# Power.net
KiCad netlist of a schematic drawn in Altium Designer
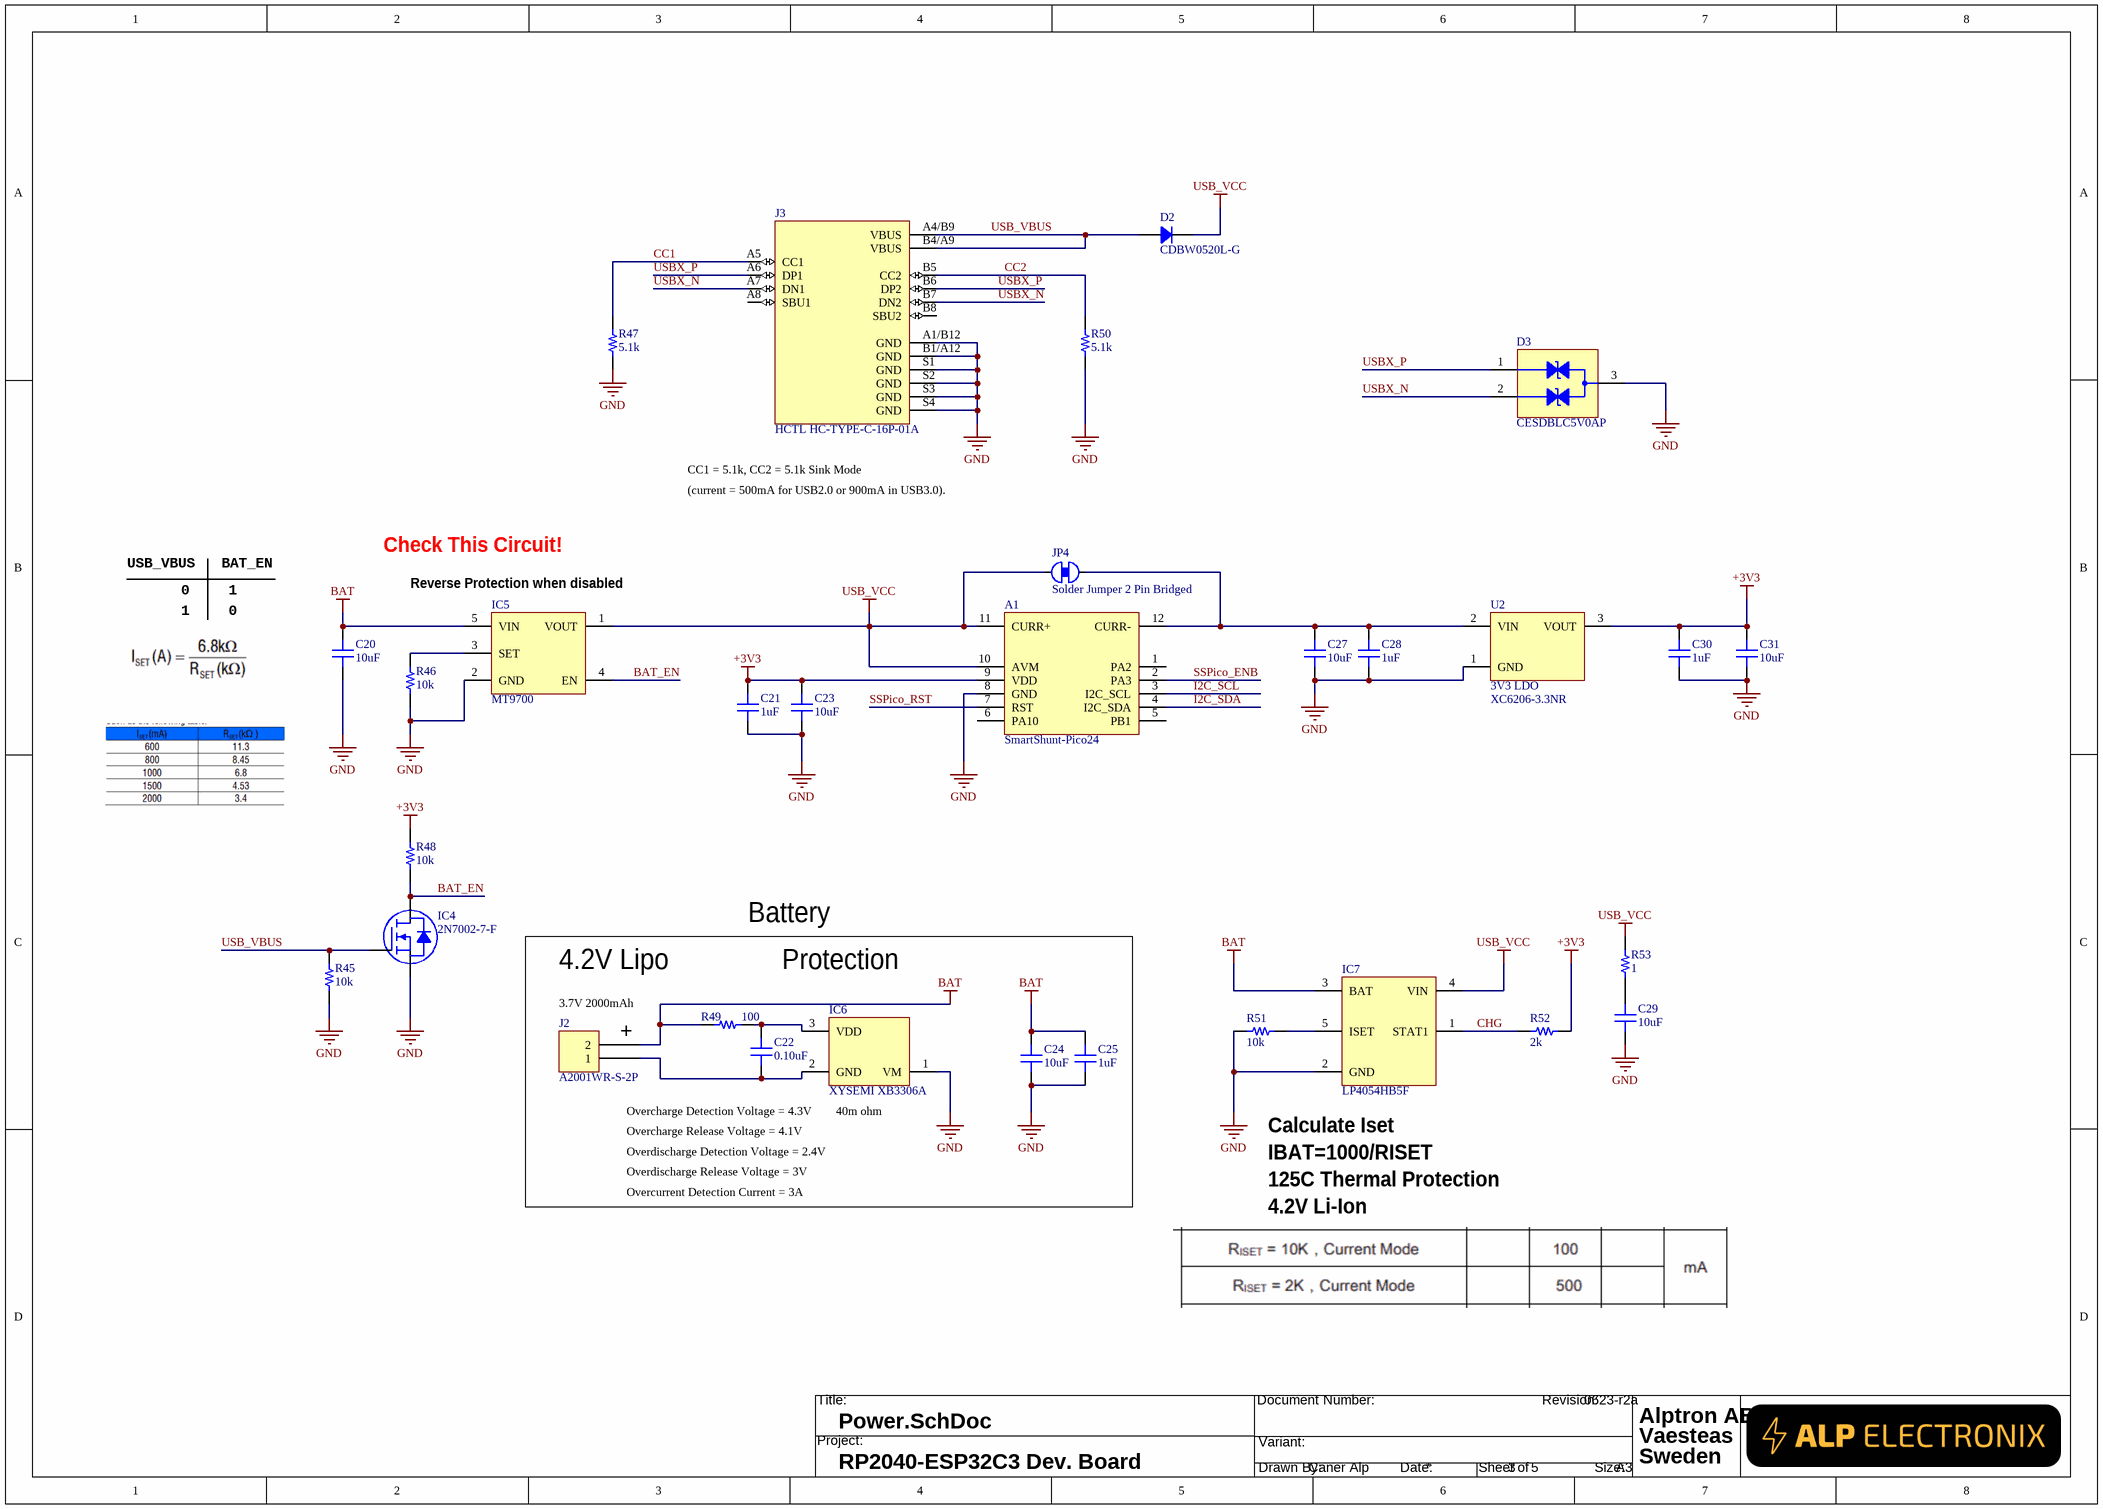
[diagram p0: Power.SchDoc]

(export (version "E")
  (design (tool "Eeschema 10.0.6"))
  (components
    (comp (ref "A1")
      (value "SmartShunt-Pico24")
      (footprint "RP2040_ESP32-C3 Dev Board PCB Lib:SmartShunt-Pico24")
      (description "Current Measurement Module")
      (libsource (lib "RP2040_ESP32-C3 Dev Board SCH Lib") (part "SmartShunt-Pico24"))
    )
    (comp (ref "C20")
      (value "10uF")
      (footprint "CAP 0603/1608")
      (description "CAP CER 10UF 6.3V X5R 0603")
      (fields
        (field (name "PART NUMBER") "GRM188R60J106ME47D")
        (field (name "MANUFACTURER") "Murata Electronics North America")
      )
      (libsource (lib "Celestial Library Database") (part "Capacitor"))
    )
    (comp (ref "C21")
      (value "1uF")
      (footprint "CAP 0402/1005")
      (description "CAP CER 1UF 6.3V X7R 0402")
      (fields
        (field (name "PART NUMBER") "GRM155R70J105KA12D")
        (field (name "MANUFACTURER") "Murata Electronics North America")
      )
      (libsource (lib "Celestial Library Database") (part "Capacitor"))
    )
    (comp (ref "C22")
      (value "0.10uF")
      (footprint "CAP 0402/1005")
      (description "CAP CER 0.1UF 10V X5R 0402")
      (fields (field (name "PART NUMBER") "LMK105BJ104KV-F") (field (name "MANUFACTURER") "Taiyo Yuden"))
      (libsource (lib "Celestial Library Database") (part "Capacitor"))
    )
    (comp (ref "C23")
      (value "10uF")
      (footprint "CAP 0603/1608")
      (description "CAP CER 10UF 6.3V X5R 0603")
      (fields
        (field (name "PART NUMBER") "GRM188R60J106ME47D")
        (field (name "MANUFACTURER") "Murata Electronics North America")
      )
      (libsource (lib "Celestial Library Database") (part "Capacitor"))
    )
    (comp (ref "C24")
      (value "10uF")
      (footprint "CAP 0603/1608")
      (description "CAP CER 10UF 6.3V X5R 0603")
      (fields
        (field (name "PART NUMBER") "GRM188R60J106ME47D")
        (field (name "MANUFACTURER") "Murata Electronics North America")
      )
      (libsource (lib "Celestial Library Database") (part "Capacitor"))
    )
    (comp (ref "C25")
      (value "1uF")
      (footprint "CAP 0402/1005")
      (description "CAP CER 1UF 6.3V X7R 0402")
      (fields
        (field (name "PART NUMBER") "GRM155R70J105KA12D")
        (field (name "MANUFACTURER") "Murata Electronics North America")
      )
      (libsource (lib "Celestial Library Database") (part "Capacitor"))
    )
    (comp (ref "C27")
      (value "10uF")
      (footprint "CAP 0603/1608")
      (description "CAP CER 10UF 6.3V X5R 0603")
      (fields
        (field (name "PART NUMBER") "GRM188R60J106ME47D")
        (field (name "MANUFACTURER") "Murata Electronics North America")
      )
      (libsource (lib "Celestial Library Database") (part "Capacitor"))
    )
    (comp (ref "C28")
      (value "1uF")
      (footprint "CAP 0402/1005")
      (description "CAP CER 1UF 6.3V X7R 0402")
      (fields
        (field (name "PART NUMBER") "GRM155R70J105KA12D")
        (field (name "MANUFACTURER") "Murata Electronics North America")
      )
      (libsource (lib "Celestial Library Database") (part "Capacitor"))
    )
    (comp (ref "C29")
      (value "10uF")
      (footprint "CAP 0603/1608")
      (description "CAP CER 10UF 6.3V X5R 0603")
      (fields
        (field (name "PART NUMBER") "GRM188R60J106ME47D")
        (field (name "MANUFACTURER") "Murata Electronics North America")
      )
      (libsource (lib "Celestial Library Database") (part "Capacitor"))
    )
    (comp (ref "C30")
      (value "1uF")
      (footprint "CAP 0402/1005")
      (description "CAP CER 1UF 6.3V X7R 0402")
      (fields
        (field (name "PART NUMBER") "GRM155R70J105KA12D")
        (field (name "MANUFACTURER") "Murata Electronics North America")
      )
      (libsource (lib "Celestial Library Database") (part "Capacitor"))
    )
    (comp (ref "C31")
      (value "10uF")
      (footprint "CAP 0603/1608")
      (description "CAP CER 10UF 6.3V X5R 0603")
      (fields
        (field (name "PART NUMBER") "GRM188R60J106ME47D")
        (field (name "MANUFACTURER") "Murata Electronics North America")
      )
      (libsource (lib "Celestial Library Database") (part "Capacitor"))
    )
    (comp (ref "D2")
      (value "CDBW0520L-G")
      (footprint "SOD-123")
      (description "DIODE SCHOTTKY 20V 500MA SOD123")
      (fields (field (name "MANUFACTURER") "Comchip Technology"))
      (libsource (lib "Celestial Altium Library - altium_library") (part "Diode"))
    )
    (comp (ref "D3")
      (value "CESDBLC5V0AP")
      (footprint "ON SEMI SOT-23-3")
      (description "TVS DIODE 24V 44V SOT23-3")
      (fields (field (name "MANUFACTURER") "ON Semiconductor"))
      (libsource (lib "Celestial Altium Library - altium_library") (part "ON SEMI SOT-23-3"))
    )
    (comp (ref "IC4")
      (value "2N7002-7-F")
      (footprint "DIODES SOT-23-3")
      (description "MOSFET N-CH 60V 115MA SOT23-3")
      (fields (field (name "MANUFACTURER") "Diodes Incorporated"))
      (libsource (lib "Celestial Library Database") (part "DIODES INC MOSFET N-CH SOT-23-3"))
    )
    (comp (ref "IC5")
      (value "MT9700")
      (footprint "RP2040_ESP32-C3 Dev Board PCB Lib:DIODES SOT-23-5 W5")
      (description "SOT-23-5 Power Distribution Switches ROHS")
      (libsource (lib "RP2040_ESP32-C3 Dev Board SCH Lib") (part "MT9700"))
    )
    (comp (ref "IC6")
      (value "XYSEMI XB3306A")
      (footprint "DIODES SOT-23-3")
      (description "IC LITHIUM BATT PROTECT SOT23-3")
      (fields (field (name "MANUFACTURER") "XYSEMI"))
      (libsource (lib "Celestial Library Database") (part "XYSEMI XB3306A"))
    )
    (comp (ref "IC7")
      (value "LP4054HB5F")
      (footprint "RP2040_ESP32-C3 Dev Board PCB Lib:DIODES SOT-23-5 W5")
      (description "600mA Standalone Linear Li-Ion Battery Charger")
      (libsource (lib "RP2040_ESP32-C3 Dev Board SCH Lib") (part "LP4054HB5F"))
    )
    (comp (ref "J2")
      (value "A2001WR-S-2P")
      (footprint "JST S2B-PH-SM4-TB")
      (description "CONN HEADER SMD R/A 2POS 2MM")
      (fields
        (field (name "PART NUMBER") "S2B-PH-SM4-TB(LF)(SN)")
        (field (name "MANUFACTURER") "JST Sales America Inc.")
      )
      (libsource (lib "Celestial Altium Library - altium_library") (part "2 Pin"))
    )
    (comp (ref "J3")
      (value "HCTL HC-TYPE-C-16P-01A")
      (footprint "RP2040_ESP32-C3 Dev Board PCB Lib:HCTL HC-TYPE-C-16P-01A")
      (description "CONN USB 2.0 TYPE-C R/A SMT")
      (fields (field (name "MANUFACTURER") "Hiro"))
      (libsource (lib "Celestial Library Database") (part "USB4110-GF-A"))
    )
    (comp (ref "JP4")
      (value "Solder Jumper 2 Pin Bridged")
      (footprint "Jumper:SolderJumper-2_P1.3mm_Bridged_RoundedPad1.0x1.5mm")
      (libsource (lib "Jumper") (part "SolderJumper_2_Bridged"))
    )
    (comp (ref "R45")
      (value "10k")
      (footprint "RES 0402/1005")
      (description "RES SMD 10K OHM 5% 1/16W 0402")
      (fields (field (name "PART NUMBER") "RC0402JR-0710KL") (field (name "MANUFACTURER") "Yageo"))
      (libsource (lib "Celestial Library Database") (part "Resistor"))
    )
    (comp (ref "R46")
      (value "10k")
      (footprint "RES 0603/1608")
      (description "RES SMD 10K OHM 5% 1/10W 0603")
      (fields
        (field (name "PART NUMBER") "ERJ-3GEYJ103V")
        (field (name "MANUFACTURER") "Panasonic Electronic Components")
      )
      (libsource (lib "Celestial Library Database") (part "Resistor"))
    )
    (comp (ref "R47")
      (value "5.1k")
      (footprint "RES 0402/1005")
      (description "RES SMD 5.1K OHM 5% 1/16W 0402")
      (fields (field (name "PART NUMBER") "RC0402JR-075K1L") (field (name "MANUFACTURER") "Yageo"))
      (libsource (lib "Celestial Library Database") (part "Resistor"))
    )
    (comp (ref "R48")
      (value "10k")
      (footprint "RES 0402/1005")
      (description "RES SMD 10K OHM 5% 1/16W 0402")
      (fields (field (name "PART NUMBER") "RC0402JR-0710KL") (field (name "MANUFACTURER") "Yageo"))
      (libsource (lib "Celestial Library Database") (part "Resistor"))
    )
    (comp (ref "R49")
      (value "100")
      (footprint "RES 0402/1005")
      (description "RES SMD 100 OHM 5% 1/16W 0402")
      (fields (field (name "PART NUMBER") "RC0402JR-07100RL") (field (name "MANUFACTURER") "Yageo"))
      (libsource (lib "Celestial Library Database") (part "Resistor"))
    )
    (comp (ref "R50")
      (value "5.1k")
      (footprint "RES 0402/1005")
      (description "RES SMD 5.1K OHM 5% 1/16W 0402")
      (fields (field (name "PART NUMBER") "RC0402JR-075K1L") (field (name "MANUFACTURER") "Yageo"))
      (libsource (lib "Celestial Library Database") (part "Resistor"))
    )
    (comp (ref "R51")
      (value "10k")
      (footprint "RES 0603/1608")
      (description "RES SMD 10K OHM 5% 1/10W 0603")
      (fields
        (field (name "PART NUMBER") "ERJ-3GEYJ103V")
        (field (name "MANUFACTURER") "Panasonic Electronic Components")
      )
      (libsource (lib "Celestial Library Database") (part "Resistor"))
    )
    (comp (ref "R52")
      (value "2k")
      (footprint "RES 0402/1005")
      (description "RES SMD 2K OHM 5% 1/16W 0402")
      (fields (field (name "PART NUMBER") "RC0402JR-072KL") (field (name "MANUFACTURER") "Yageo"))
      (libsource (lib "Celestial Library Database") (part "Resistor"))
    )
    (comp (ref "R53")
      (value "1")
      (footprint "RES 0402/1005")
      (description "RES SMD 1 OHM 5% 1/16W 0402")
      (fields (field (name "PART NUMBER") "RC0402JR-071RL") (field (name "MANUFACTURER") "Yageo"))
      (libsource (lib "Celestial Library Database") (part "Resistor"))
    )
    (comp (ref "U2")
      (value "3V3 LDO")
      (footprint "RP2040_ESP32-C3 Dev Board PCB Lib:DIODES SOT-23-3")
      (fields (field (name "MPN") "XC6206-3.3NR"))
      (libsource (lib "RP2040_ESP32-C3 Dev Board SCH Lib") (part "XC6206-3.3NR"))
    )
  )
  (nets
    (net (code "1") (name "+3V3") (class "Default")
      (node (ref "A1") (pin "9") (pinfunction "VDD_9") (pintype "passive"))
      (node (ref "C21") (pin "2") (pinfunction "2_2") (pintype "passive"))
      (node (ref "C23") (pin "2") (pinfunction "2_2") (pintype "passive"))
      (node (ref "C30") (pin "2") (pinfunction "2_2") (pintype "passive"))
      (node (ref "C31") (pin "2") (pinfunction "2_2") (pintype "passive"))
      (node (ref "R48") (pin "2") (pinfunction "2_2") (pintype "passive"))
      (node (ref "R52") (pin "2") (pinfunction "2_2") (pintype "passive"))
      (node (ref "U2") (pin "3") (pinfunction "VOUT_3") (pintype "passive"))
    )
    (net (code "2") (name "/BAT_EN") (class "Default")
      (node (ref "IC4") (pin "2") (pinfunction "D_2") (pintype "passive"))
      (node (ref "IC5") (pin "4") (pinfunction "EN_4") (pintype "passive"))
      (node (ref "R48") (pin "1") (pinfunction "1_1") (pintype "passive"))
    )
    (net (code "3") (name "/CC1") (class "Default")
      (node (ref "J3") (pin "A5") (pinfunction "CC1_A5") (pintype "bidirectional"))
      (node (ref "R47") (pin "2") (pinfunction "2_2") (pintype "passive"))
    )
    (net (code "4") (name "/CC2") (class "Default")
      (node (ref "J3") (pin "B5") (pinfunction "CC2_B5") (pintype "bidirectional"))
      (node (ref "R50") (pin "2") (pinfunction "2_2") (pintype "passive"))
    )
    (net (code "5") (name "/CHG") (class "Default")
      (node (ref "IC7") (pin "1") (pinfunction "STAT1_1") (pintype "passive"))
      (node (ref "R52") (pin "1") (pinfunction "1_1") (pintype "passive"))
    )
    (net (code "6") (name "/I2C_SCL") (class "Default")
      (node (ref "A1") (pin "3") (pinfunction "I2C_SCL_3") (pintype "passive"))
    )
    (net (code "7") (name "/I2C_SDA") (class "Default")
      (node (ref "A1") (pin "4") (pinfunction "I2C_SDA_4") (pintype "passive"))
    )
    (net (code "8") (name "/SSPico_ENB") (class "Default")
      (node (ref "A1") (pin "2") (pinfunction "PA3_2") (pintype "passive"))
    )
    (net (code "9") (name "/SSPico_RST") (class "Default")
      (node (ref "A1") (pin "7") (pinfunction "RST_7") (pintype "passive"))
    )
    (net (code "10") (name "/USBX_N") (class "Default")
      (node (ref "D3") (pin "2") (pinfunction "GND_2") (pintype "passive"))
      (node (ref "J3") (pin "A7") (pinfunction "DN1_A7") (pintype "bidirectional"))
      (node (ref "J3") (pin "B7") (pinfunction "DN2_B7") (pintype "bidirectional"))
    )
    (net (code "11") (name "/USBX_P") (class "Default")
      (node (ref "D3") (pin "1") (pinfunction "I/O_1_1") (pintype "passive"))
      (node (ref "J3") (pin "A6") (pinfunction "DP1_A6") (pintype "bidirectional"))
      (node (ref "J3") (pin "B6") (pinfunction "DP2_B6") (pintype "bidirectional"))
    )
    (net (code "12") (name "/USB_VBUS") (class "Default")
      (node (ref "D2") (pin "1") (pinfunction "1_1") (pintype "passive"))
      (node (ref "IC4") (pin "1") (pinfunction "G_1") (pintype "passive"))
      (node (ref "J3") (pin "A4/B9") (pinfunction "VBUS_A4/B9") (pintype "power_in"))
      (node (ref "J3") (pin "B4/A9") (pinfunction "VBUS_B4/A9") (pintype "power_in"))
      (node (ref "R45") (pin "2") (pinfunction "2_2") (pintype "passive"))
    )
    (net (code "13") (name "BAT") (class "Default")
      (node (ref "C20") (pin "2") (pinfunction "2_2") (pintype "passive"))
      (node (ref "C24") (pin "2") (pinfunction "2_2") (pintype "passive"))
      (node (ref "C25") (pin "2") (pinfunction "2_2") (pintype "passive"))
      (node (ref "IC5") (pin "5") (pinfunction "VIN_5") (pintype "passive"))
      (node (ref "IC7") (pin "3") (pinfunction "BAT_3") (pintype "passive"))
      (node (ref "J2") (pin "2") (pinfunction "2_2") (pintype "passive"))
      (node (ref "R49") (pin "1") (pinfunction "1_1") (pintype "passive"))
    )
    (net (code "14") (name "GND") (class "Default")
      (node (ref "A1") (pin "8") (pinfunction "GND_8") (pintype "passive"))
      (node (ref "C20") (pin "1") (pinfunction "1_1") (pintype "passive"))
      (node (ref "C21") (pin "1") (pinfunction "1_1") (pintype "passive"))
      (node (ref "C23") (pin "1") (pinfunction "1_1") (pintype "passive"))
      (node (ref "C24") (pin "1") (pinfunction "1_1") (pintype "passive"))
      (node (ref "C25") (pin "1") (pinfunction "1_1") (pintype "passive"))
      (node (ref "C27") (pin "1") (pinfunction "1_1") (pintype "passive"))
      (node (ref "C28") (pin "1") (pinfunction "1_1") (pintype "passive"))
      (node (ref "C29") (pin "1") (pinfunction "1_1") (pintype "passive"))
      (node (ref "C30") (pin "1") (pinfunction "1_1") (pintype "passive"))
      (node (ref "C31") (pin "1") (pinfunction "1_1") (pintype "passive"))
      (node (ref "D3") (pin "3") (pinfunction "I/O_2_3") (pintype "passive"))
      (node (ref "IC4") (pin "3") (pinfunction "S_3") (pintype "passive"))
      (node (ref "IC5") (pin "2") (pinfunction "GND_2") (pintype "passive"))
      (node (ref "IC6") (pin "1") (pinfunction "VM_1") (pintype "passive"))
      (node (ref "IC7") (pin "2") (pinfunction "GND_2") (pintype "passive"))
      (node (ref "J3") (pin "A1/B12") (pinfunction "GND_A1/B12") (pintype "power_in"))
      (node (ref "J3") (pin "B1/A12") (pinfunction "GND_B1/A12") (pintype "power_in"))
      (node (ref "J3") (pin "S1") (pinfunction "GND_S1") (pintype "power_in"))
      (node (ref "J3") (pin "S2") (pinfunction "GND_S2") (pintype "power_in"))
      (node (ref "J3") (pin "S3") (pinfunction "GND_S3") (pintype "power_in"))
      (node (ref "J3") (pin "S4") (pinfunction "GND_S4") (pintype "power_in"))
      (node (ref "R45") (pin "1") (pinfunction "1_1") (pintype "passive"))
      (node (ref "R46") (pin "1") (pinfunction "1_1") (pintype "passive"))
      (node (ref "R47") (pin "1") (pinfunction "1_1") (pintype "passive"))
      (node (ref "R50") (pin "1") (pinfunction "1_1") (pintype "passive"))
      (node (ref "R51") (pin "1") (pinfunction "1_1") (pintype "passive"))
      (node (ref "U2") (pin "1") (pinfunction "GND_1") (pintype "passive"))
    )
    (net (code "15") (name "Net-(A1-CURR-)") (class "Default")
      (node (ref "A1") (pin "12") (pinfunction "CURR-_12") (pintype "passive"))
      (node (ref "C27") (pin "2") (pinfunction "2_2") (pintype "passive"))
      (node (ref "C28") (pin "2") (pinfunction "2_2") (pintype "passive"))
      (node (ref "JP4") (pin "2") (pinfunction "B_2") (pintype "passive"))
      (node (ref "U2") (pin "2") (pinfunction "VIN_2") (pintype "passive"))
    )
    (net (code "16") (name "Net-(C29-Pad2)") (class "Default")
      (node (ref "C29") (pin "2") (pinfunction "2_2") (pintype "passive"))
      (node (ref "R53") (pin "1") (pinfunction "1_1") (pintype "passive"))
    )
    (net (code "17") (name "Net-(IC5-SET)") (class "Default")
      (node (ref "IC5") (pin "3") (pinfunction "SET_3") (pintype "passive"))
      (node (ref "R46") (pin "2") (pinfunction "2_2") (pintype "passive"))
    )
    (net (code "18") (name "Net-(IC6-GND)") (class "Default")
      (node (ref "C22") (pin "1") (pinfunction "1_1") (pintype "passive"))
      (node (ref "IC6") (pin "2") (pinfunction "GND_2") (pintype "passive"))
      (node (ref "J2") (pin "1") (pinfunction "1_1") (pintype "passive"))
    )
    (net (code "19") (name "Net-(IC6-VDD)") (class "Default")
      (node (ref "C22") (pin "2") (pinfunction "2_2") (pintype "passive"))
      (node (ref "IC6") (pin "3") (pinfunction "VDD_3") (pintype "passive"))
      (node (ref "R49") (pin "2") (pinfunction "2_2") (pintype "passive"))
    )
    (net (code "20") (name "Net-(IC7-ISET)") (class "Default")
      (node (ref "IC7") (pin "5") (pinfunction "ISET_5") (pintype "passive"))
      (node (ref "R51") (pin "2") (pinfunction "2_2") (pintype "passive"))
    )
    (net (code "21") (name "USB_VCC") (class "Default")
      (node (ref "A1") (pin "10") (pinfunction "AVM_10") (pintype "passive"))
      (node (ref "A1") (pin "11") (pinfunction "CURR+_11") (pintype "passive"))
      (node (ref "D2") (pin "2") (pinfunction "2_2") (pintype "passive"))
      (node (ref "IC5") (pin "1") (pinfunction "VOUT_1") (pintype "passive"))
      (node (ref "IC7") (pin "4") (pinfunction "VIN_4") (pintype "passive"))
      (node (ref "JP4") (pin "1") (pinfunction "A_1") (pintype "passive"))
      (node (ref "R53") (pin "2") (pinfunction "2_2") (pintype "passive"))
    )
    (net (code "22") (name "unconnected-(A1-PA2-Pad1)") (class "Default")
      (node (ref "A1") (pin "1") (pinfunction "PA2_1") (pintype "passive"))
    )
    (net (code "23") (name "unconnected-(A1-PA10-Pad6)") (class "Default")
      (node (ref "A1") (pin "6") (pinfunction "PA10_6") (pintype "passive"))
    )
    (net (code "24") (name "unconnected-(A1-PB1-Pad5)") (class "Default")
      (node (ref "A1") (pin "5") (pinfunction "PB1_5") (pintype "passive"))
    )
    (net (code "25") (name "unconnected-(J3-SBU1-PadA8)") (class "Default")
      (node (ref "J3") (pin "A8") (pinfunction "SBU1_A8") (pintype "bidirectional"))
    )
    (net (code "26") (name "unconnected-(J3-SBU2-PadB8)") (class "Default")
      (node (ref "J3") (pin "B8") (pinfunction "SBU2_B8") (pintype "bidirectional"))
    )
  )
)
